# SCH_metroscope.net
KiCad netlist of a schematic drawn in EasyEDA
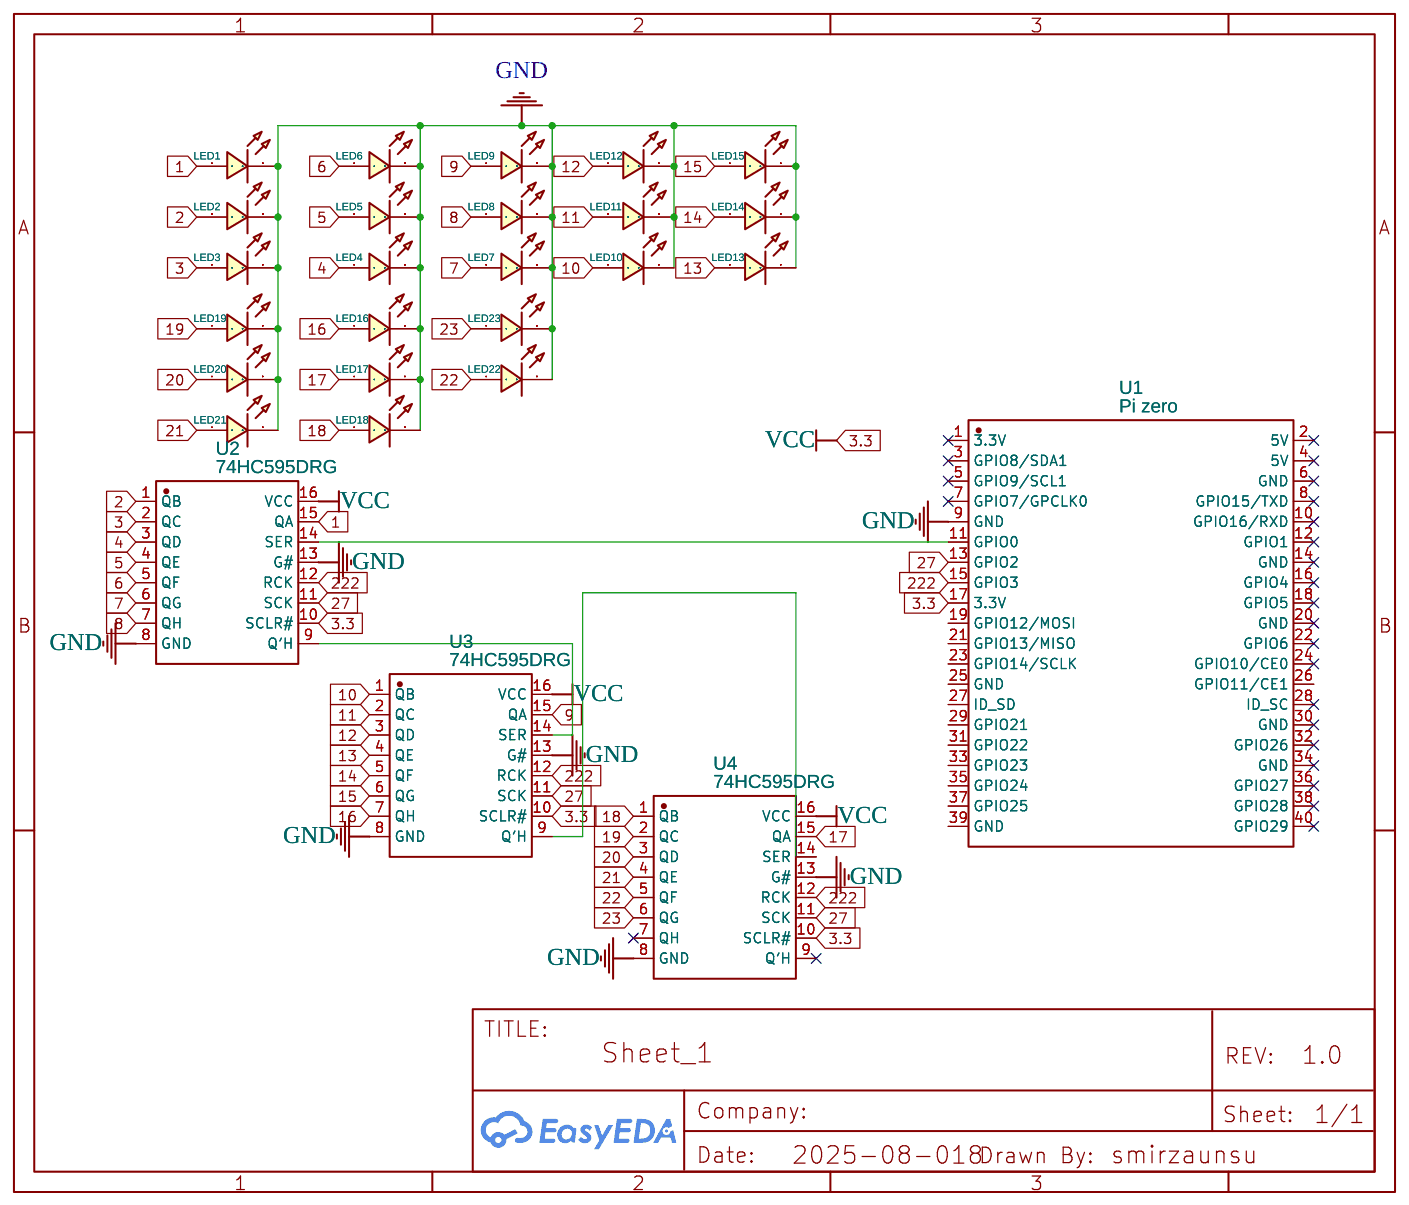
[diagram p0: schematic sheet]

(export (version "E")
  (design (tool "Eeschema 10.0.6"))
  (components
    (comp (ref "LED1")
      (value "LED-0603_R")
      (fields
        (field (name "Manufacturer Part") "19-217/R6C-AL1M2VY/3T")
        (field (name "Manufacturer") "EVERLIGHT(台湾亿光)")
      )
      (libsource (lib "") (part "LED-0603_R"))
    )
    (comp (ref "LED2")
      (value "LED-0603_R")
      (fields
        (field (name "Manufacturer Part") "19-217/R6C-AL1M2VY/3T")
        (field (name "Manufacturer") "EVERLIGHT(台湾亿光)")
      )
      (libsource (lib "") (part "LED-0603_R"))
    )
    (comp (ref "LED3")
      (value "LED-0603_R")
      (fields
        (field (name "Manufacturer Part") "19-217/R6C-AL1M2VY/3T")
        (field (name "Manufacturer") "EVERLIGHT(台湾亿光)")
      )
      (libsource (lib "") (part "LED-0603_R"))
    )
    (comp (ref "LED4")
      (value "LED-0603_R")
      (fields
        (field (name "Manufacturer Part") "19-217/R6C-AL1M2VY/3T")
        (field (name "Manufacturer") "EVERLIGHT(台湾亿光)")
      )
      (libsource (lib "") (part "LED-0603_R"))
    )
    (comp (ref "LED5")
      (value "LED-0603_R")
      (fields
        (field (name "Manufacturer Part") "19-217/R6C-AL1M2VY/3T")
        (field (name "Manufacturer") "EVERLIGHT(台湾亿光)")
      )
      (libsource (lib "") (part "LED-0603_R"))
    )
    (comp (ref "LED6")
      (value "LED-0603_R")
      (fields
        (field (name "Manufacturer Part") "19-217/R6C-AL1M2VY/3T")
        (field (name "Manufacturer") "EVERLIGHT(台湾亿光)")
      )
      (libsource (lib "") (part "LED-0603_R"))
    )
    (comp (ref "LED7")
      (value "LED-0603_R")
      (fields
        (field (name "Manufacturer Part") "19-217/R6C-AL1M2VY/3T")
        (field (name "Manufacturer") "EVERLIGHT(台湾亿光)")
      )
      (libsource (lib "") (part "LED-0603_R"))
    )
    (comp (ref "LED8")
      (value "LED-0603_R")
      (fields
        (field (name "Manufacturer Part") "19-217/R6C-AL1M2VY/3T")
        (field (name "Manufacturer") "EVERLIGHT(台湾亿光)")
      )
      (libsource (lib "") (part "LED-0603_R"))
    )
    (comp (ref "LED9")
      (value "LED-0603_R")
      (fields
        (field (name "Manufacturer Part") "19-217/R6C-AL1M2VY/3T")
        (field (name "Manufacturer") "EVERLIGHT(台湾亿光)")
      )
      (libsource (lib "") (part "LED-0603_R"))
    )
    (comp (ref "LED10")
      (value "LED-0603_R")
      (fields
        (field (name "Manufacturer Part") "19-217/R6C-AL1M2VY/3T")
        (field (name "Manufacturer") "EVERLIGHT(台湾亿光)")
      )
      (libsource (lib "") (part "LED-0603_R"))
    )
    (comp (ref "LED11")
      (value "LED-0603_R")
      (fields
        (field (name "Manufacturer Part") "19-217/R6C-AL1M2VY/3T")
        (field (name "Manufacturer") "EVERLIGHT(台湾亿光)")
      )
      (libsource (lib "") (part "LED-0603_R"))
    )
    (comp (ref "LED12")
      (value "LED-0603_R")
      (fields
        (field (name "Manufacturer Part") "19-217/R6C-AL1M2VY/3T")
        (field (name "Manufacturer") "EVERLIGHT(台湾亿光)")
      )
      (libsource (lib "") (part "LED-0603_R"))
    )
    (comp (ref "LED13")
      (value "LED-0603_R")
      (fields
        (field (name "Manufacturer Part") "19-217/R6C-AL1M2VY/3T")
        (field (name "Manufacturer") "EVERLIGHT(台湾亿光)")
      )
      (libsource (lib "") (part "LED-0603_R"))
    )
    (comp (ref "LED14")
      (value "LED-0603_R")
      (fields
        (field (name "Manufacturer Part") "19-217/R6C-AL1M2VY/3T")
        (field (name "Manufacturer") "EVERLIGHT(台湾亿光)")
      )
      (libsource (lib "") (part "LED-0603_R"))
    )
    (comp (ref "LED15")
      (value "LED-0603_R")
      (fields
        (field (name "Manufacturer Part") "19-217/R6C-AL1M2VY/3T")
        (field (name "Manufacturer") "EVERLIGHT(台湾亿光)")
      )
      (libsource (lib "") (part "LED-0603_R"))
    )
    (comp (ref "LED16")
      (value "LED-0603_R")
      (fields
        (field (name "Manufacturer Part") "19-217/R6C-AL1M2VY/3T")
        (field (name "Manufacturer") "EVERLIGHT(台湾亿光)")
      )
      (libsource (lib "") (part "LED-0603_R"))
    )
    (comp (ref "LED17")
      (value "LED-0603_R")
      (fields
        (field (name "Manufacturer Part") "19-217/R6C-AL1M2VY/3T")
        (field (name "Manufacturer") "EVERLIGHT(台湾亿光)")
      )
      (libsource (lib "") (part "LED-0603_R"))
    )
    (comp (ref "LED18")
      (value "LED-0603_R")
      (fields
        (field (name "Manufacturer Part") "19-217/R6C-AL1M2VY/3T")
        (field (name "Manufacturer") "EVERLIGHT(台湾亿光)")
      )
      (libsource (lib "") (part "LED-0603_R"))
    )
    (comp (ref "LED19")
      (value "LED-0603_R")
      (fields
        (field (name "Manufacturer Part") "19-217/R6C-AL1M2VY/3T")
        (field (name "Manufacturer") "EVERLIGHT(台湾亿光)")
      )
      (libsource (lib "") (part "LED-0603_R"))
    )
    (comp (ref "LED20")
      (value "LED-0603_R")
      (fields
        (field (name "Manufacturer Part") "19-217/R6C-AL1M2VY/3T")
        (field (name "Manufacturer") "EVERLIGHT(台湾亿光)")
      )
      (libsource (lib "") (part "LED-0603_R"))
    )
    (comp (ref "LED21")
      (value "LED-0603_R")
      (fields
        (field (name "Manufacturer Part") "19-217/R6C-AL1M2VY/3T")
        (field (name "Manufacturer") "EVERLIGHT(台湾亿光)")
      )
      (libsource (lib "") (part "LED-0603_R"))
    )
    (comp (ref "LED22")
      (value "LED-0603_R")
      (fields
        (field (name "Manufacturer Part") "19-217/R6C-AL1M2VY/3T")
        (field (name "Manufacturer") "EVERLIGHT(台湾亿光)")
      )
      (libsource (lib "") (part "LED-0603_R"))
    )
    (comp (ref "LED23")
      (value "LED-0603_R")
      (fields
        (field (name "Manufacturer Part") "19-217/R6C-AL1M2VY/3T")
        (field (name "Manufacturer") "EVERLIGHT(台湾亿光)")
      )
      (libsource (lib "") (part "LED-0603_R"))
    )
    (comp (ref "U1") (value "Pi zero") (libsource (lib "") (part "Pi zero")))
    (comp (ref "U2")
      (value "74HC595DRG")
      (fields (field (name "Manufacturer") "HGC(深圳汉芯)"))
      (libsource (lib "") (part "74HC595DRG"))
    )
    (comp (ref "U3")
      (value "74HC595DRG")
      (fields (field (name "Manufacturer") "HGC(深圳汉芯)"))
      (libsource (lib "") (part "74HC595DRG"))
    )
    (comp (ref "U4")
      (value "74HC595DRG")
      (fields (field (name "Manufacturer") "HGC(深圳汉芯)"))
      (libsource (lib "") (part "74HC595DRG"))
    )
  )
  (nets
    (net (code "1") (name "1") (class "Default")
      (node (ref "LED1") (pin "1") (pinfunction "1_1") (pintype "unspecified"))
      (node (ref "U2") (pin "15") (pinfunction "QA_15") (pintype "unspecified"))
    )
    (net (code "2") (name "2") (class "Default")
      (node (ref "LED2") (pin "1") (pinfunction "1_1") (pintype "unspecified"))
      (node (ref "U2") (pin "1") (pinfunction "QB_1") (pintype "unspecified"))
    )
    (net (code "3") (name "3") (class "Default")
      (node (ref "LED3") (pin "1") (pinfunction "1_1") (pintype "unspecified"))
      (node (ref "U2") (pin "2") (pinfunction "QC_2") (pintype "unspecified"))
    )
    (net (code "4") (name "3.3") (class "Default")
      (node (ref "U1") (pin "17") (pinfunction "3.3V_17") (pintype "unspecified"))
      (node (ref "U2") (pin "10") (pinfunction "SCLR#_10") (pintype "unspecified"))
      (node (ref "U2") (pin "16") (pinfunction "VCC_16") (pintype "unspecified"))
      (node (ref "U3") (pin "10") (pinfunction "SCLR#_10") (pintype "unspecified"))
      (node (ref "U3") (pin "16") (pinfunction "VCC_16") (pintype "unspecified"))
      (node (ref "U4") (pin "10") (pinfunction "SCLR#_10") (pintype "unspecified"))
      (node (ref "U4") (pin "16") (pinfunction "VCC_16") (pintype "unspecified"))
    )
    (net (code "5") (name "4") (class "Default")
      (node (ref "LED4") (pin "1") (pinfunction "1_1") (pintype "unspecified"))
      (node (ref "U2") (pin "3") (pinfunction "QD_3") (pintype "unspecified"))
    )
    (net (code "6") (name "5") (class "Default")
      (node (ref "LED5") (pin "1") (pinfunction "1_1") (pintype "unspecified"))
      (node (ref "U2") (pin "4") (pinfunction "QE_4") (pintype "unspecified"))
    )
    (net (code "7") (name "6") (class "Default")
      (node (ref "LED6") (pin "1") (pinfunction "1_1") (pintype "unspecified"))
      (node (ref "U2") (pin "5") (pinfunction "QF_5") (pintype "unspecified"))
    )
    (net (code "8") (name "7") (class "Default")
      (node (ref "LED7") (pin "1") (pinfunction "1_1") (pintype "unspecified"))
      (node (ref "U2") (pin "6") (pinfunction "QG_6") (pintype "unspecified"))
    )
    (net (code "9") (name "8") (class "Default")
      (node (ref "LED8") (pin "1") (pinfunction "1_1") (pintype "unspecified"))
      (node (ref "U2") (pin "7") (pinfunction "QH_7") (pintype "unspecified"))
    )
    (net (code "10") (name "9") (class "Default")
      (node (ref "LED9") (pin "1") (pinfunction "1_1") (pintype "unspecified"))
      (node (ref "U3") (pin "15") (pinfunction "QA_15") (pintype "unspecified"))
    )
    (net (code "11") (name "10") (class "Default")
      (node (ref "LED10") (pin "1") (pinfunction "1_1") (pintype "unspecified"))
      (node (ref "U3") (pin "1") (pinfunction "QB_1") (pintype "unspecified"))
    )
    (net (code "12") (name "11") (class "Default")
      (node (ref "LED11") (pin "1") (pinfunction "1_1") (pintype "unspecified"))
      (node (ref "U3") (pin "2") (pinfunction "QC_2") (pintype "unspecified"))
    )
    (net (code "13") (name "12") (class "Default")
      (node (ref "LED12") (pin "1") (pinfunction "1_1") (pintype "unspecified"))
      (node (ref "U3") (pin "3") (pinfunction "QD_3") (pintype "unspecified"))
    )
    (net (code "14") (name "13") (class "Default")
      (node (ref "LED13") (pin "1") (pinfunction "1_1") (pintype "unspecified"))
      (node (ref "U3") (pin "4") (pinfunction "QE_4") (pintype "unspecified"))
    )
    (net (code "15") (name "14") (class "Default")
      (node (ref "LED14") (pin "1") (pinfunction "1_1") (pintype "unspecified"))
      (node (ref "U3") (pin "5") (pinfunction "QF_5") (pintype "unspecified"))
    )
    (net (code "16") (name "15") (class "Default")
      (node (ref "LED15") (pin "1") (pinfunction "1_1") (pintype "unspecified"))
      (node (ref "U3") (pin "6") (pinfunction "QG_6") (pintype "unspecified"))
    )
    (net (code "17") (name "16") (class "Default")
      (node (ref "LED16") (pin "1") (pinfunction "1_1") (pintype "unspecified"))
      (node (ref "U3") (pin "7") (pinfunction "QH_7") (pintype "unspecified"))
    )
    (net (code "18") (name "17") (class "Default")
      (node (ref "LED17") (pin "1") (pinfunction "1_1") (pintype "unspecified"))
      (node (ref "U4") (pin "15") (pinfunction "QA_15") (pintype "unspecified"))
    )
    (net (code "19") (name "18") (class "Default")
      (node (ref "LED18") (pin "1") (pinfunction "1_1") (pintype "unspecified"))
      (node (ref "U4") (pin "1") (pinfunction "QB_1") (pintype "unspecified"))
    )
    (net (code "20") (name "19") (class "Default")
      (node (ref "LED19") (pin "1") (pinfunction "1_1") (pintype "unspecified"))
      (node (ref "U4") (pin "2") (pinfunction "QC_2") (pintype "unspecified"))
    )
    (net (code "21") (name "20") (class "Default")
      (node (ref "LED20") (pin "1") (pinfunction "1_1") (pintype "unspecified"))
      (node (ref "U4") (pin "3") (pinfunction "QD_3") (pintype "unspecified"))
    )
    (net (code "22") (name "21") (class "Default")
      (node (ref "LED21") (pin "1") (pinfunction "1_1") (pintype "unspecified"))
      (node (ref "U4") (pin "4") (pinfunction "QE_4") (pintype "unspecified"))
    )
    (net (code "23") (name "22") (class "Default")
      (node (ref "LED22") (pin "1") (pinfunction "1_1") (pintype "unspecified"))
      (node (ref "U4") (pin "5") (pinfunction "QF_5") (pintype "unspecified"))
    )
    (net (code "24") (name "23") (class "Default")
      (node (ref "LED23") (pin "1") (pinfunction "1_1") (pintype "unspecified"))
      (node (ref "U4") (pin "6") (pinfunction "QG_6") (pintype "unspecified"))
    )
    (net (code "25") (name "27") (class "Default")
      (node (ref "U1") (pin "13") (pinfunction "GPIO2_13") (pintype "unspecified"))
      (node (ref "U2") (pin "11") (pinfunction "SCK_11") (pintype "unspecified"))
      (node (ref "U3") (pin "11") (pinfunction "SCK_11") (pintype "unspecified"))
      (node (ref "U4") (pin "11") (pinfunction "SCK_11") (pintype "unspecified"))
    )
    (net (code "26") (name "222") (class "Default")
      (node (ref "U1") (pin "15") (pinfunction "GPIO3_15") (pintype "unspecified"))
      (node (ref "U2") (pin "12") (pinfunction "RCK_12") (pintype "unspecified"))
      (node (ref "U3") (pin "12") (pinfunction "RCK_12") (pintype "unspecified"))
      (node (ref "U4") (pin "12") (pinfunction "RCK_12") (pintype "unspecified"))
    )
    (net (code "27") (name "GND") (class "Default")
      (node (ref "LED1") (pin "2") (pinfunction "2_2") (pintype "unspecified"))
      (node (ref "LED10") (pin "2") (pinfunction "2_2") (pintype "unspecified"))
      (node (ref "LED11") (pin "2") (pinfunction "2_2") (pintype "unspecified"))
      (node (ref "LED12") (pin "2") (pinfunction "2_2") (pintype "unspecified"))
      (node (ref "LED13") (pin "2") (pinfunction "2_2") (pintype "unspecified"))
      (node (ref "LED14") (pin "2") (pinfunction "2_2") (pintype "unspecified"))
      (node (ref "LED15") (pin "2") (pinfunction "2_2") (pintype "unspecified"))
      (node (ref "LED16") (pin "2") (pinfunction "2_2") (pintype "unspecified"))
      (node (ref "LED17") (pin "2") (pinfunction "2_2") (pintype "unspecified"))
      (node (ref "LED18") (pin "2") (pinfunction "2_2") (pintype "unspecified"))
      (node (ref "LED19") (pin "2") (pinfunction "2_2") (pintype "unspecified"))
      (node (ref "LED2") (pin "2") (pinfunction "2_2") (pintype "unspecified"))
      (node (ref "LED20") (pin "2") (pinfunction "2_2") (pintype "unspecified"))
      (node (ref "LED21") (pin "2") (pinfunction "2_2") (pintype "unspecified"))
      (node (ref "LED22") (pin "2") (pinfunction "2_2") (pintype "unspecified"))
      (node (ref "LED23") (pin "2") (pinfunction "2_2") (pintype "unspecified"))
      (node (ref "LED3") (pin "2") (pinfunction "2_2") (pintype "unspecified"))
      (node (ref "LED4") (pin "2") (pinfunction "2_2") (pintype "unspecified"))
      (node (ref "LED5") (pin "2") (pinfunction "2_2") (pintype "unspecified"))
      (node (ref "LED6") (pin "2") (pinfunction "2_2") (pintype "unspecified"))
      (node (ref "LED7") (pin "2") (pinfunction "2_2") (pintype "unspecified"))
      (node (ref "LED8") (pin "2") (pinfunction "2_2") (pintype "unspecified"))
      (node (ref "LED9") (pin "2") (pinfunction "2_2") (pintype "unspecified"))
      (node (ref "U1") (pin "9") (pinfunction "GND_9") (pintype "unspecified"))
      (node (ref "U2") (pin "13") (pinfunction "G#_13") (pintype "unspecified"))
      (node (ref "U2") (pin "8") (pinfunction "GND_8") (pintype "unspecified"))
      (node (ref "U3") (pin "13") (pinfunction "G#_13") (pintype "unspecified"))
      (node (ref "U3") (pin "8") (pinfunction "GND_8") (pintype "unspecified"))
      (node (ref "U4") (pin "13") (pinfunction "G#_13") (pintype "unspecified"))
      (node (ref "U4") (pin "8") (pinfunction "GND_8") (pintype "unspecified"))
    )
    (net (code "28") (name "Net-(U1-GPIO0)") (class "Default")
      (node (ref "U1") (pin "11") (pinfunction "GPIO0_11") (pintype "unspecified"))
      (node (ref "U2") (pin "14") (pinfunction "SER_14") (pintype "unspecified"))
    )
    (net (code "29") (name "Net-(U2-Q′H)") (class "Default")
      (node (ref "U2") (pin "9") (pinfunction "Q′H_9") (pintype "unspecified"))
      (node (ref "U3") (pin "14") (pinfunction "SER_14") (pintype "unspecified"))
    )
    (net (code "30") (name "Net-(U3-Q′H)") (class "Default")
      (node (ref "U3") (pin "9") (pinfunction "Q′H_9") (pintype "unspecified"))
      (node (ref "U4") (pin "14") (pinfunction "SER_14") (pintype "unspecified"))
    )
    (net (code "31") (name "unconnected-(U1-3.3V-Pad1)") (class "Default")
      (node (ref "U1") (pin "1") (pinfunction "3.3V_1") (pintype "unspecified+no_connect"))
    )
    (net (code "32") (name "unconnected-(U1-5V-Pad2)") (class "Default")
      (node (ref "U1") (pin "2") (pinfunction "5V_2") (pintype "unspecified+no_connect"))
    )
    (net (code "33") (name "unconnected-(U1-5V-Pad4)") (class "Default")
      (node (ref "U1") (pin "4") (pinfunction "5V_4") (pintype "unspecified+no_connect"))
    )
    (net (code "34") (name "unconnected-(U1-GND-Pad6)") (class "Default")
      (node (ref "U1") (pin "6") (pinfunction "GND_6") (pintype "unspecified+no_connect"))
    )
    (net (code "35") (name "unconnected-(U1-GND-Pad14)") (class "Default")
      (node (ref "U1") (pin "14") (pinfunction "GND_14") (pintype "unspecified+no_connect"))
    )
    (net (code "36") (name "unconnected-(U1-GND-Pad20)") (class "Default")
      (node (ref "U1") (pin "20") (pinfunction "GND_20") (pintype "unspecified+no_connect"))
    )
    (net (code "37") (name "unconnected-(U1-GND-Pad25)") (class "Default")
      (node (ref "U1") (pin "25") (pinfunction "GND_25") (pintype "unspecified"))
    )
    (net (code "38") (name "unconnected-(U1-GND-Pad30)") (class "Default")
      (node (ref "U1") (pin "30") (pinfunction "GND_30") (pintype "unspecified+no_connect"))
    )
    (net (code "39") (name "unconnected-(U1-GND-Pad34)") (class "Default")
      (node (ref "U1") (pin "34") (pinfunction "GND_34") (pintype "unspecified+no_connect"))
    )
    (net (code "40") (name "unconnected-(U1-GND-Pad39)") (class "Default")
      (node (ref "U1") (pin "39") (pinfunction "GND_39") (pintype "unspecified"))
    )
    (net (code "41") (name "unconnected-(U1-GPIO1-Pad12)") (class "Default")
      (node (ref "U1") (pin "12") (pinfunction "GPIO1_12") (pintype "unspecified+no_connect"))
    )
    (net (code "42") (name "unconnected-(U1-GPIO4-Pad16)") (class "Default")
      (node (ref "U1") (pin "16") (pinfunction "GPIO4_16") (pintype "unspecified+no_connect"))
    )
    (net (code "43") (name "unconnected-(U1-GPIO5-Pad18)") (class "Default")
      (node (ref "U1") (pin "18") (pinfunction "GPIO5_18") (pintype "unspecified+no_connect"))
    )
    (net (code "44") (name "unconnected-(U1-GPIO6-Pad22)") (class "Default")
      (node (ref "U1") (pin "22") (pinfunction "GPIO6_22") (pintype "unspecified+no_connect"))
    )
    (net (code "45") (name "unconnected-(U1-GPIO7{slash}GPCLK0-Pad7)") (class "Default")
      (node (ref "U1") (pin "7") (pinfunction "GPIO7/GPCLK0_7") (pintype "unspecified+no_connect"))
    )
    (net (code "46") (name "unconnected-(U1-GPIO8{slash}SDA1-Pad3)") (class "Default")
      (node (ref "U1") (pin "3") (pinfunction "GPIO8/SDA1_3") (pintype "unspecified+no_connect"))
    )
    (net (code "47") (name "unconnected-(U1-GPIO9{slash}SCL1-Pad5)") (class "Default")
      (node (ref "U1") (pin "5") (pinfunction "GPIO9/SCL1_5") (pintype "unspecified+no_connect"))
    )
    (net (code "48") (name "unconnected-(U1-GPIO10{slash}CE0-Pad24)") (class "Default")
      (node (ref "U1") (pin "24") (pinfunction "GPIO10/CE0_24") (pintype "unspecified+no_connect"))
    )
    (net (code "49") (name "unconnected-(U1-GPIO11{slash}CE1-Pad26)") (class "Default")
      (node (ref "U1") (pin "26") (pinfunction "GPIO11/CE1_26") (pintype "unspecified"))
    )
    (net (code "50") (name "unconnected-(U1-GPIO12{slash}MOSI-Pad19)") (class "Default")
      (node (ref "U1") (pin "19") (pinfunction "GPIO12/MOSI_19") (pintype "unspecified"))
    )
    (net (code "51") (name "unconnected-(U1-GPIO13{slash}MISO-Pad21)") (class "Default")
      (node (ref "U1") (pin "21") (pinfunction "GPIO13/MISO_21") (pintype "unspecified"))
    )
    (net (code "52") (name "unconnected-(U1-GPIO14{slash}SCLK-Pad23)") (class "Default")
      (node (ref "U1") (pin "23") (pinfunction "GPIO14/SCLK_23") (pintype "unspecified"))
    )
    (net (code "53") (name "unconnected-(U1-GPIO15{slash}TXD-Pad8)") (class "Default")
      (node (ref "U1") (pin "8") (pinfunction "GPIO15/TXD_8") (pintype "unspecified+no_connect"))
    )
    (net (code "54") (name "unconnected-(U1-GPIO16{slash}RXD-Pad10)") (class "Default")
      (node (ref "U1") (pin "10") (pinfunction "GPIO16/RXD_10") (pintype "unspecified+no_connect"))
    )
    (net (code "55") (name "unconnected-(U1-GPIO21-Pad29)") (class "Default")
      (node (ref "U1") (pin "29") (pinfunction "GPIO21_29") (pintype "unspecified"))
    )
    (net (code "56") (name "unconnected-(U1-GPIO22-Pad31)") (class "Default")
      (node (ref "U1") (pin "31") (pinfunction "GPIO22_31") (pintype "unspecified"))
    )
    (net (code "57") (name "unconnected-(U1-GPIO23-Pad33)") (class "Default")
      (node (ref "U1") (pin "33") (pinfunction "GPIO23_33") (pintype "unspecified"))
    )
    (net (code "58") (name "unconnected-(U1-GPIO24-Pad35)") (class "Default")
      (node (ref "U1") (pin "35") (pinfunction "GPIO24_35") (pintype "unspecified"))
    )
    (net (code "59") (name "unconnected-(U1-GPIO25-Pad37)") (class "Default")
      (node (ref "U1") (pin "37") (pinfunction "GPIO25_37") (pintype "unspecified"))
    )
    (net (code "60") (name "unconnected-(U1-GPIO26-Pad32)") (class "Default")
      (node (ref "U1") (pin "32") (pinfunction "GPIO26_32") (pintype "unspecified+no_connect"))
    )
    (net (code "61") (name "unconnected-(U1-GPIO27-Pad36)") (class "Default")
      (node (ref "U1") (pin "36") (pinfunction "GPIO27_36") (pintype "unspecified+no_connect"))
    )
    (net (code "62") (name "unconnected-(U1-GPIO28-Pad38)") (class "Default")
      (node (ref "U1") (pin "38") (pinfunction "GPIO28_38") (pintype "unspecified+no_connect"))
    )
    (net (code "63") (name "unconnected-(U1-GPIO29-Pad40)") (class "Default")
      (node (ref "U1") (pin "40") (pinfunction "GPIO29_40") (pintype "unspecified+no_connect"))
    )
    (net (code "64") (name "unconnected-(U1-ID_SC-Pad28)") (class "Default")
      (node (ref "U1") (pin "28") (pinfunction "ID_SC_28") (pintype "unspecified+no_connect"))
    )
    (net (code "65") (name "unconnected-(U1-ID_SD-Pad27)") (class "Default")
      (node (ref "U1") (pin "27") (pinfunction "ID_SD_27") (pintype "unspecified"))
    )
    (net (code "66") (name "unconnected-(U4-QH-Pad7)") (class "Default")
      (node (ref "U4") (pin "7") (pinfunction "QH_7") (pintype "unspecified+no_connect"))
    )
    (net (code "67") (name "unconnected-(U4-Q′H-Pad9)") (class "Default")
      (node (ref "U4") (pin "9") (pinfunction "Q′H_9") (pintype "unspecified+no_connect"))
    )
  )
)
